# SP2_BUCKs_GPU_LOG_CPU-B.net
KiCad netlist of a schematic drawn in Altium Designer
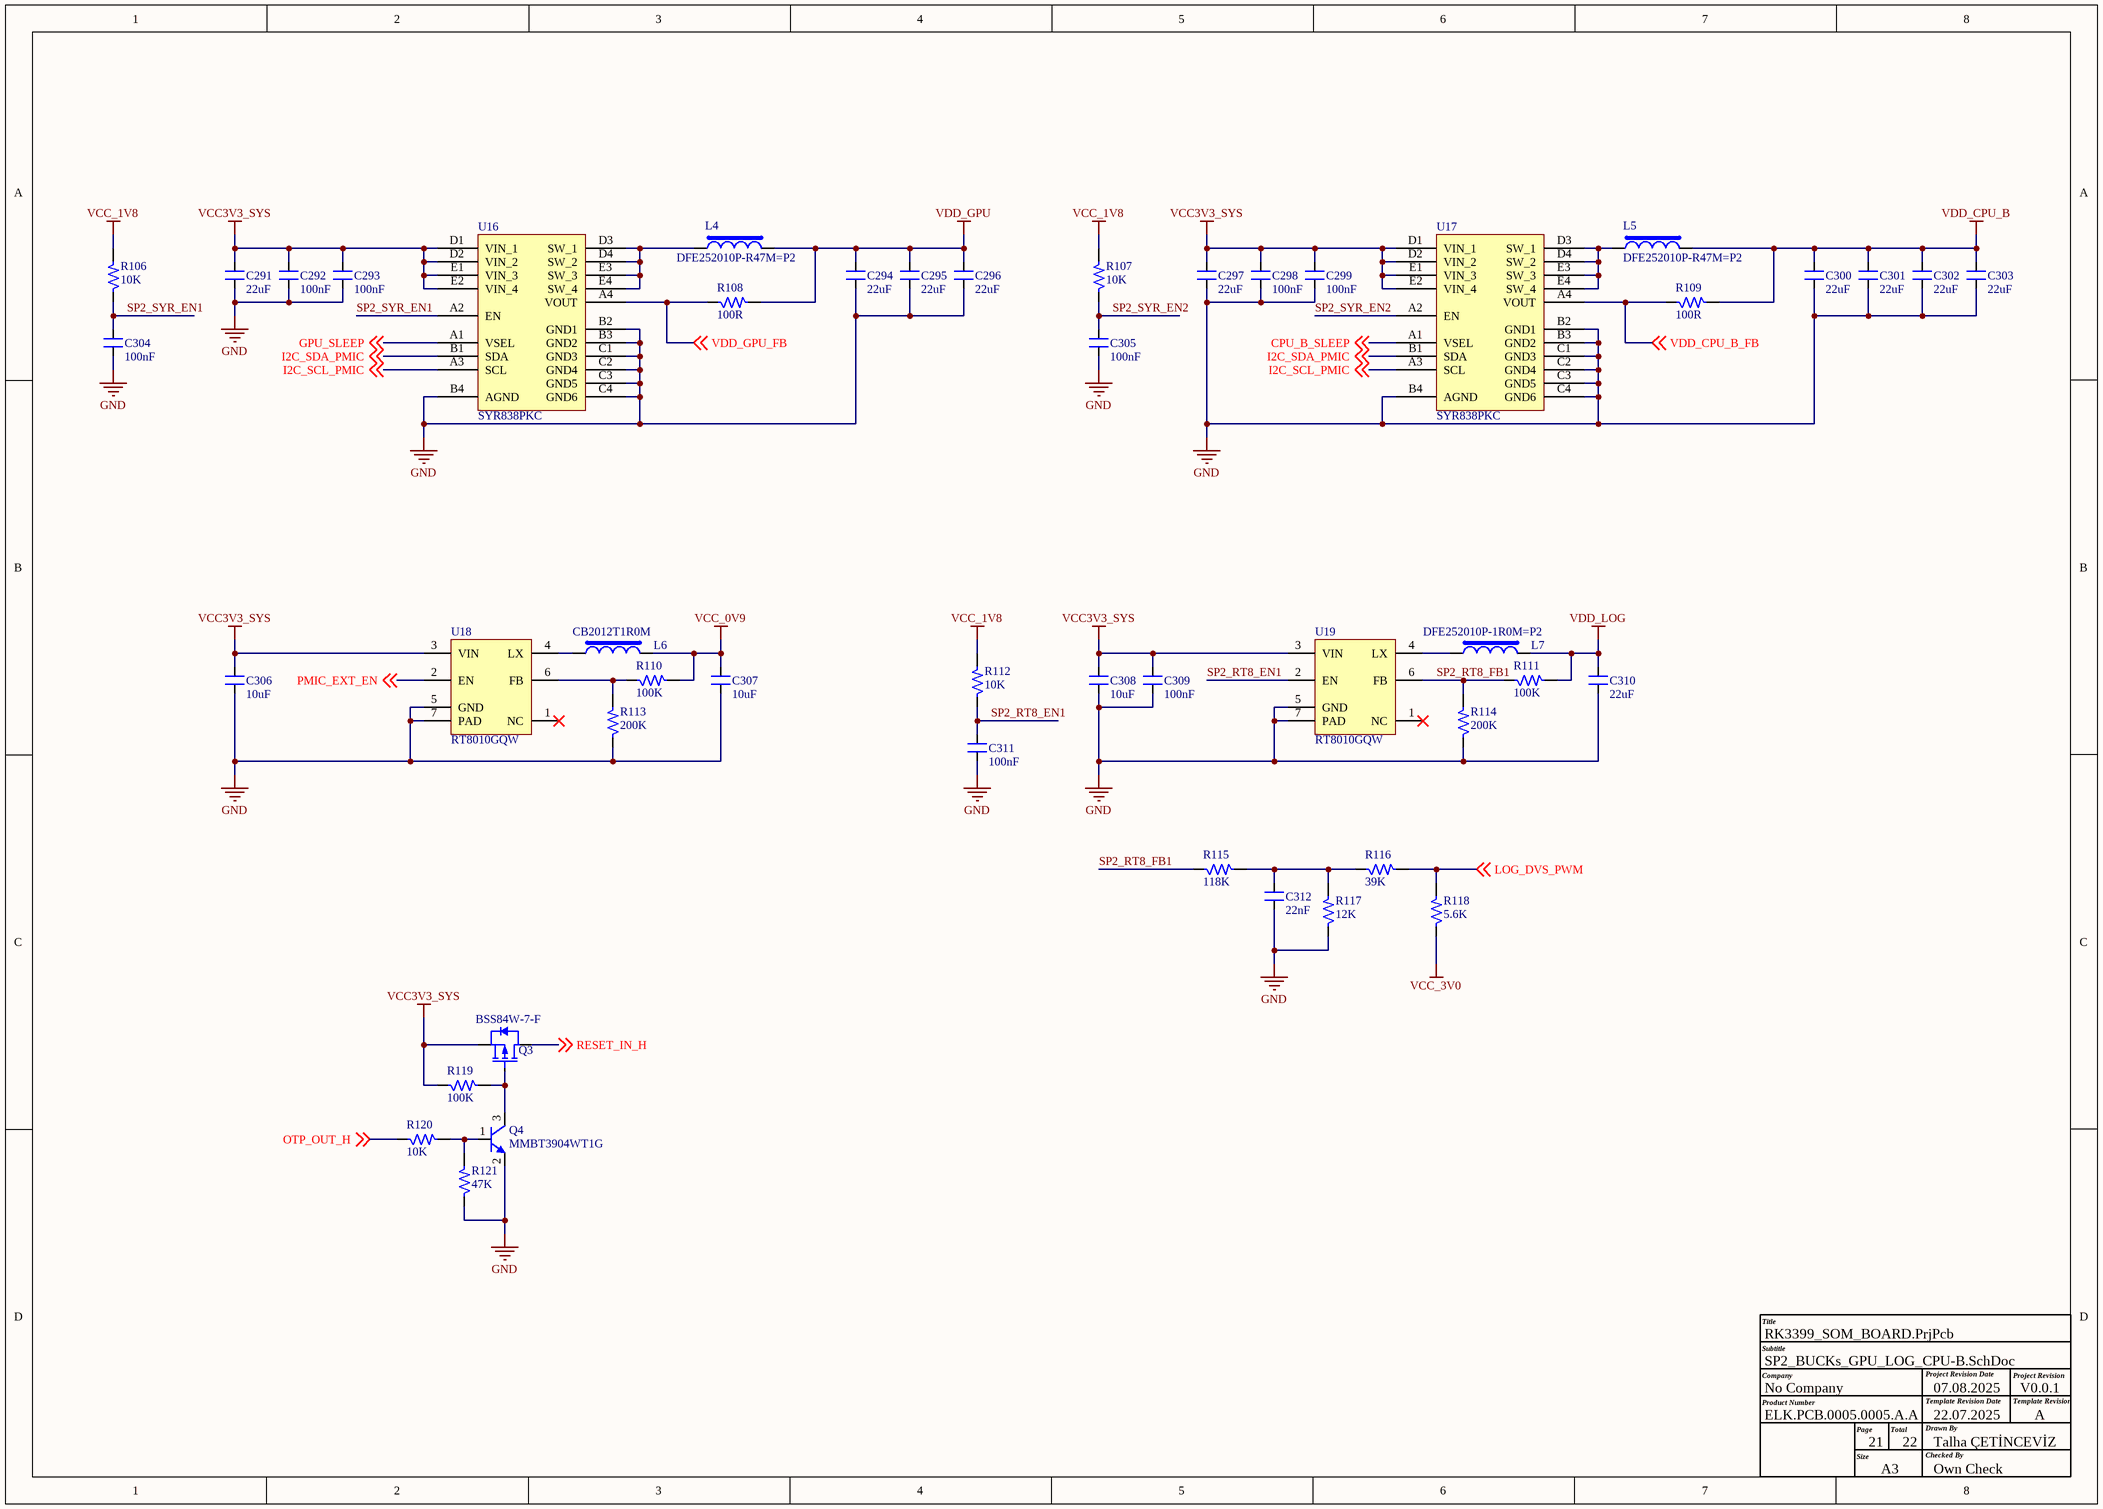
[diagram p0: SP2_BUCKs_GPU_LOG_CPU-B.SchDoc]

(export (version "E")
  (design (tool "Eeschema 10.0.6"))
  (components
    (comp (ref "C291")
      (value "22uF")
      (footprint "CAP_0603")
      (description "22µF ±20% 10V Ceramic Capacitor X5R 0603 (1608 Metric)")
      (fields
        (field (name "MANUFACTURER") "Murata Electronics")
        (field (name "MANUFACTURER PART NUMBER") "GRM188R61A226ME15D")
      )
      (libsource (lib "EsteemPCB_SOM_Course_intlib") (part "CAP_22uF-10V-20%-0603"))
    )
    (comp (ref "C292")
      (value "100nF")
      (footprint "CAP_0402")
      (description "0.1µF ±10% 25V Ceramic Capacitor X7R 0402 (1005 Metric)")
      (fields
        (field (name "MANUFACTURER") "Walsin Technology Corporation")
        (field (name "MANUFACTURER PART NUMBER") "0402B104K250CT")
      )
      (libsource (lib "EsteemPCB_SOM_Course_intlib") (part "CAP_100nF-25V-10%-0402"))
    )
    (comp (ref "C293")
      (value "100nF")
      (footprint "CAP_0402")
      (description "0.1µF ±10% 25V Ceramic Capacitor X7R 0402 (1005 Metric)")
      (fields
        (field (name "MANUFACTURER") "Walsin Technology Corporation")
        (field (name "MANUFACTURER PART NUMBER") "0402B104K250CT")
      )
      (libsource (lib "EsteemPCB_SOM_Course_intlib") (part "CAP_100nF-25V-10%-0402"))
    )
    (comp (ref "C294")
      (value "22uF")
      (footprint "CAP_0603")
      (description "22µF ±20% 10V Ceramic Capacitor X5R 0603 (1608 Metric)")
      (fields
        (field (name "MANUFACTURER") "Murata Electronics")
        (field (name "MANUFACTURER PART NUMBER") "GRM188R61A226ME15D")
      )
      (libsource (lib "EsteemPCB_SOM_Course_intlib") (part "CAP_22uF-10V-20%-0603"))
    )
    (comp (ref "C295")
      (value "22uF")
      (footprint "CAP_0603")
      (description "22µF ±20% 10V Ceramic Capacitor X5R 0603 (1608 Metric)")
      (fields
        (field (name "MANUFACTURER") "Murata Electronics")
        (field (name "MANUFACTURER PART NUMBER") "GRM188R61A226ME15D")
      )
      (libsource (lib "EsteemPCB_SOM_Course_intlib") (part "CAP_22uF-10V-20%-0603"))
    )
    (comp (ref "C296")
      (value "22uF")
      (footprint "CAP_0603")
      (description "22µF ±20% 10V Ceramic Capacitor X5R 0603 (1608 Metric)")
      (fields
        (field (name "MANUFACTURER") "Murata Electronics")
        (field (name "MANUFACTURER PART NUMBER") "GRM188R61A226ME15D")
      )
      (libsource (lib "EsteemPCB_SOM_Course_intlib") (part "CAP_22uF-10V-20%-0603"))
    )
    (comp (ref "C297")
      (value "22uF")
      (footprint "CAP_0603")
      (description "22µF ±20% 10V Ceramic Capacitor X5R 0603 (1608 Metric)")
      (fields
        (field (name "MANUFACTURER") "Murata Electronics")
        (field (name "MANUFACTURER PART NUMBER") "GRM188R61A226ME15D")
      )
      (libsource (lib "EsteemPCB_SOM_Course_intlib") (part "CAP_22uF-10V-20%-0603"))
    )
    (comp (ref "C298")
      (value "100nF")
      (footprint "CAP_0402")
      (description "0.1µF ±10% 25V Ceramic Capacitor X7R 0402 (1005 Metric)")
      (fields
        (field (name "MANUFACTURER") "Walsin Technology Corporation")
        (field (name "MANUFACTURER PART NUMBER") "0402B104K250CT")
      )
      (libsource (lib "EsteemPCB_SOM_Course_intlib") (part "CAP_100nF-25V-10%-0402"))
    )
    (comp (ref "C299")
      (value "100nF")
      (footprint "CAP_0402")
      (description "0.1µF ±10% 25V Ceramic Capacitor X7R 0402 (1005 Metric)")
      (fields
        (field (name "MANUFACTURER") "Walsin Technology Corporation")
        (field (name "MANUFACTURER PART NUMBER") "0402B104K250CT")
      )
      (libsource (lib "EsteemPCB_SOM_Course_intlib") (part "CAP_100nF-25V-10%-0402"))
    )
    (comp (ref "C300")
      (value "22uF")
      (footprint "CAP_0603")
      (description "22µF ±20% 10V Ceramic Capacitor X5R 0603 (1608 Metric)")
      (fields
        (field (name "MANUFACTURER") "Murata Electronics")
        (field (name "MANUFACTURER PART NUMBER") "GRM188R61A226ME15D")
      )
      (libsource (lib "EsteemPCB_SOM_Course_intlib") (part "CAP_22uF-10V-20%-0603"))
    )
    (comp (ref "C301")
      (value "22uF")
      (footprint "CAP_0603")
      (description "22µF ±20% 10V Ceramic Capacitor X5R 0603 (1608 Metric)")
      (fields
        (field (name "MANUFACTURER") "Murata Electronics")
        (field (name "MANUFACTURER PART NUMBER") "GRM188R61A226ME15D")
      )
      (libsource (lib "EsteemPCB_SOM_Course_intlib") (part "CAP_22uF-10V-20%-0603"))
    )
    (comp (ref "C302")
      (value "22uF")
      (footprint "CAP_0603")
      (description "22µF ±20% 10V Ceramic Capacitor X5R 0603 (1608 Metric)")
      (fields
        (field (name "MANUFACTURER") "Murata Electronics")
        (field (name "MANUFACTURER PART NUMBER") "GRM188R61A226ME15D")
      )
      (libsource (lib "EsteemPCB_SOM_Course_intlib") (part "CAP_22uF-10V-20%-0603"))
    )
    (comp (ref "C303")
      (value "22uF")
      (footprint "CAP_0603")
      (description "22µF ±20% 10V Ceramic Capacitor X5R 0603 (1608 Metric)")
      (fields
        (field (name "MANUFACTURER") "Murata Electronics")
        (field (name "MANUFACTURER PART NUMBER") "GRM188R61A226ME15D")
      )
      (libsource (lib "EsteemPCB_SOM_Course_intlib") (part "CAP_22uF-10V-20%-0603"))
    )
    (comp (ref "C304")
      (value "100nF")
      (footprint "CAP_0402")
      (description "0.1µF ±10% 25V Ceramic Capacitor X7R 0402 (1005 Metric)")
      (fields
        (field (name "MANUFACTURER") "Walsin Technology Corporation")
        (field (name "MANUFACTURER PART NUMBER") "0402B104K250CT")
      )
      (libsource (lib "EsteemPCB_SOM_Course_intlib") (part "CAP_100nF-25V-10%-0402"))
    )
    (comp (ref "C305")
      (value "100nF")
      (footprint "CAP_0402")
      (description "0.1µF ±10% 25V Ceramic Capacitor X7R 0402 (1005 Metric)")
      (fields
        (field (name "MANUFACTURER") "Walsin Technology Corporation")
        (field (name "MANUFACTURER PART NUMBER") "0402B104K250CT")
      )
      (libsource (lib "EsteemPCB_SOM_Course_intlib") (part "CAP_100nF-25V-10%-0402"))
    )
    (comp (ref "C306")
      (value "10uF")
      (footprint "CAP_0402")
      (description "10µF ±20% 10V Ceramic Capacitor X5R 0402 (1005 Metric)")
      (fields
        (field (name "MANUFACTURER PART NUMBER") "CL05A106MP5NUNC")
        (field (name "MANUFACTURER") "Samsung Electro-Mechanics")
      )
      (libsource (lib "EsteemPCB_SOM_Course_intlib") (part "CAP_10uF-10V-20%-0402"))
    )
    (comp (ref "C307")
      (value "10uF")
      (footprint "CAP_0402")
      (description "10µF ±20% 10V Ceramic Capacitor X5R 0402 (1005 Metric)")
      (fields
        (field (name "MANUFACTURER PART NUMBER") "CL05A106MP5NUNC")
        (field (name "MANUFACTURER") "Samsung Electro-Mechanics")
      )
      (libsource (lib "EsteemPCB_SOM_Course_intlib") (part "CAP_10uF-10V-20%-0402"))
    )
    (comp (ref "C308")
      (value "10uF")
      (footprint "CAP_0402")
      (description "10µF ±20% 10V Ceramic Capacitor X5R 0402 (1005 Metric)")
      (fields
        (field (name "MANUFACTURER PART NUMBER") "CL05A106MP5NUNC")
        (field (name "MANUFACTURER") "Samsung Electro-Mechanics")
      )
      (libsource (lib "EsteemPCB_SOM_Course_intlib") (part "CAP_10uF-10V-20%-0402"))
    )
    (comp (ref "C309")
      (value "100nF")
      (footprint "CAP_0402")
      (description "0.1µF ±10% 25V Ceramic Capacitor X7R 0402 (1005 Metric)")
      (fields
        (field (name "MANUFACTURER") "Walsin Technology Corporation")
        (field (name "MANUFACTURER PART NUMBER") "0402B104K250CT")
      )
      (libsource (lib "EsteemPCB_SOM_Course_intlib") (part "CAP_100nF-25V-10%-0402"))
    )
    (comp (ref "C310")
      (value "22uF")
      (footprint "CAP_0603")
      (description "22µF ±20% 10V Ceramic Capacitor X5R 0603 (1608 Metric)")
      (fields
        (field (name "MANUFACTURER") "Murata Electronics")
        (field (name "MANUFACTURER PART NUMBER") "GRM188R61A226ME15D")
      )
      (libsource (lib "EsteemPCB_SOM_Course_intlib") (part "CAP_22uF-10V-20%-0603"))
    )
    (comp (ref "C311")
      (value "100nF")
      (footprint "CAP_0402")
      (description "0.1µF ±10% 25V Ceramic Capacitor X7R 0402 (1005 Metric)")
      (fields
        (field (name "MANUFACTURER") "Walsin Technology Corporation")
        (field (name "MANUFACTURER PART NUMBER") "0402B104K250CT")
      )
      (libsource (lib "EsteemPCB_SOM_Course_intlib") (part "CAP_100nF-25V-10%-0402"))
    )
    (comp (ref "C312")
      (value "22nF")
      (footprint "CAP_0402")
      (description "0.022µF ±10% 10V Ceramic Capacitor X7R 0402 (1005 Metric)")
      (fields
        (field (name "MANUFACTURER") "Samsung Electro-Mechanics")
        (field (name "MANUFACTURER PART NUMBER") "CL05B223KP5NNNC")
      )
      (libsource (lib "EsteemPCB_SOM_Course_intlib") (part "CAP_22nF-10V-10%-0402"))
    )
    (comp (ref "L4")
      (value "DFE252010P-R47M=P2")
      (footprint "IND_1008")
      (description "470nH Shielded Wirewound Inductor 5A 35mOhm Max 1008 (2520 Metric)")
      (fields (field (name "MANUFACTURER") "Murata Electronics"))
      (libsource (lib "EsteemPCB_SOM_Course_intlib") (part "IND_470nH-5A-20%-1008"))
    )
    (comp (ref "L5")
      (value "DFE252010P-R47M=P2")
      (footprint "IND_1008")
      (description "470nH Shielded Wirewound Inductor 5A 35mOhm Max 1008 (2520 Metric)")
      (fields (field (name "MANUFACTURER") "Murata Electronics"))
      (libsource (lib "EsteemPCB_SOM_Course_intlib") (part "IND_470nH-5A-20%-1008"))
    )
    (comp (ref "L6")
      (value "CB2012T1R0M")
      (footprint "IND_0805")
      (description "1uH ±20% 500mA 150mΩ 0805 Inductors (SMD) RoHS")
      (fields (field (name "MANUFACTURER") "Taiyo Yuden"))
      (libsource (lib "EsteemPCB_SOM_Course_intlib") (part "IND_1uF-0.5A-20%-0805"))
    )
    (comp (ref "L7")
      (value "DFE252010P-1R0M=P2")
      (footprint "IND_1008")
      (description "1µH Shielded Wirewound Inductor 3.8A 54mOhm Max 1008 (2520 Metric)")
      (fields (field (name "MANUFACTURER") "Murata Electronics"))
      (libsource (lib "EsteemPCB_SOM_Course_intlib") (part "IND_1uH-3.8A-20%-1008"))
    )
    (comp (ref "Q3")
      (value "BSS84W-7-F")
      (footprint "SOT-323-3")
      (description "P-Channel 50V 130mA (Ta) 200mW (Ta) Surface Mount SOT-323")
      (fields (field (name "MANUFACTURER") "Diodes Incorporated"))
      (libsource (lib "EsteemPCB_SOM_Course_intlib") (part "MOSFET-P_50V-130mA-SOT-323"))
    )
    (comp (ref "Q4")
      (value "MMBT3904WT1G")
      (footprint "SOT-323-3")
      (description "Bipolar Transistors - BJT 200mA 60V NPN")
      (fields (field (name "MANUFACTURER") "ON Semiconductor"))
      (libsource (lib "EsteemPCB_SOM_Course_intlib") (part "TRNS-NPN_60V-0.2A-SOT323"))
    )
    (comp (ref "R106")
      (value "10K")
      (footprint "RES_0402")
      (description "10 kOhms ±1% 0.1W, 1/10W Chip Resistor 0402 (1005 Metric) Anti-Sulfur Thin Film")
      (fields
        (field (name "MANUFACTURER") "Vishay Beyschlag/Draloric/BC Components")
        (field (name "MANUFACTURER PART NUMBER") "MCS04020C1002FE000")
      )
      (libsource (lib "EsteemPCB_SOM_Course_intlib") (part "RES_10K-0.1W-1%-0402"))
    )
    (comp (ref "R107")
      (value "10K")
      (footprint "RES_0402")
      (description "10 kOhms ±1% 0.1W, 1/10W Chip Resistor 0402 (1005 Metric) Anti-Sulfur Thin Film")
      (fields
        (field (name "MANUFACTURER") "Vishay Beyschlag/Draloric/BC Components")
        (field (name "MANUFACTURER PART NUMBER") "MCS04020C1002FE000")
      )
      (libsource (lib "EsteemPCB_SOM_Course_intlib") (part "RES_10K-0.1W-1%-0402"))
    )
    (comp (ref "R108")
      (value "100R")
      (footprint "RES_0402")
      (fields
        (field (name "MANUFACTURER") "KOA Speer Electronics, Inc.")
        (field (name "MANUFACTURER PART NUMBER") "RK73H1ETTP1000F")
      )
      (libsource (lib "EsteemPCB_SOM_Course_intlib") (part "RES_100R-0.1W-1%-0402"))
    )
    (comp (ref "R109")
      (value "100R")
      (footprint "RES_0402")
      (fields
        (field (name "MANUFACTURER") "KOA Speer Electronics, Inc.")
        (field (name "MANUFACTURER PART NUMBER") "RK73H1ETTP1000F")
      )
      (libsource (lib "EsteemPCB_SOM_Course_intlib") (part "RES_100R-0.1W-1%-0402"))
    )
    (comp (ref "R110")
      (value "100K")
      (footprint "RES_0402")
      (description "100 kOhms ±1% 0.1W, 1/10W Chip Resistor 0402 (1005 Metric) Anti-Sulfur Thin Film")
      (fields
        (field (name "MANUFACTURER") "Vishay Beyschlag/Draloric/BC Components")
        (field (name "MANUFACTURER PART NUMBER") "MCS04020C1003FE000")
      )
      (libsource (lib "EsteemPCB_SOM_Course_intlib") (part "RES_100K-0.1W-1%-0402"))
    )
    (comp (ref "R111")
      (value "100K")
      (footprint "RES_0402")
      (description "100 kOhms ±1% 0.1W, 1/10W Chip Resistor 0402 (1005 Metric) Anti-Sulfur Thin Film")
      (fields
        (field (name "MANUFACTURER") "Vishay Beyschlag/Draloric/BC Components")
        (field (name "MANUFACTURER PART NUMBER") "MCS04020C1003FE000")
      )
      (libsource (lib "EsteemPCB_SOM_Course_intlib") (part "RES_100K-0.1W-1%-0402"))
    )
    (comp (ref "R112")
      (value "10K")
      (footprint "RES_0402")
      (description "10 kOhms ±1% 0.1W, 1/10W Chip Resistor 0402 (1005 Metric) Anti-Sulfur Thin Film")
      (fields
        (field (name "MANUFACTURER") "Vishay Beyschlag/Draloric/BC Components")
        (field (name "MANUFACTURER PART NUMBER") "MCS04020C1002FE000")
      )
      (libsource (lib "EsteemPCB_SOM_Course_intlib") (part "RES_10K-0.1W-1%-0402"))
    )
    (comp (ref "R113")
      (value "200K")
      (footprint "RES_0402")
      (description "200 kOhms ±1% 0.1W, 1/10W Chip Resistor 0402 (1005 Metric) Automotive AEC-Q200 Thick Film")
      (fields
        (field (name "MANUFACTURER") "Panasonic Electronic Components")
        (field (name "MANUFACTURER PART NUMBER") "ERJ-2RKF2003X")
      )
      (libsource (lib "EsteemPCB_SOM_Course_intlib") (part "RES_200K-0.1W-1%-0402"))
    )
    (comp (ref "R114")
      (value "200K")
      (footprint "RES_0402")
      (description "200 kOhms ±1% 0.1W, 1/10W Chip Resistor 0402 (1005 Metric) Automotive AEC-Q200 Thick Film")
      (fields
        (field (name "MANUFACTURER") "Panasonic Electronic Components")
        (field (name "MANUFACTURER PART NUMBER") "ERJ-2RKF2003X")
      )
      (libsource (lib "EsteemPCB_SOM_Course_intlib") (part "RES_200K-0.1W-1%-0402"))
    )
    (comp (ref "R115")
      (value "118K")
      (footprint "RES_0402")
      (fields
        (field (name "MANUFACTURER") "KOA Speer Electronics, Inc.")
        (field (name "MANUAFCTURER PART NUMBER") "RK73H1ETTP1183F")
      )
      (libsource (lib "EsteemPCB_SOM_Course_intlib") (part "RES_118K-0.1W-1%-0402"))
    )
    (comp (ref "R116")
      (value "39K")
      (footprint "RES_0402")
      (fields
        (field (name "MANUFACTURER") "KOA Speer Electronics, Inc.")
        (field (name "MANUFACTURER PART NUMBER") "RK73H1ETTP3902F")
      )
      (libsource (lib "EsteemPCB_SOM_Course_intlib") (part "RES_39K-0.1W-1%-0402"))
    )
    (comp (ref "R117")
      (value "12K")
      (footprint "RES_0402")
      (description "12 kOhms ±1% 0.1W, 1/10W Chip Resistor 0402 (1005 Metric) Anti-Sulfur Thin Film")
      (fields
        (field (name "MANUFACTURER") "Vishay Beyschlag/Draloric/BC Components")
        (field (name "MANUFACTURER PART NUMBER") "MCS04020C1202FE000")
      )
      (libsource (lib "EsteemPCB_SOM_Course_intlib") (part "RES_12K-0.1W-1%-0402"))
    )
    (comp (ref "R118")
      (value "5.6K")
      (footprint "RES_0402")
      (fields
        (field (name "MANUFACTURER") "KOA Speer Electronics, Inc.")
        (field (name "MANUFACTURER PART NUMBER") "RK73H1ETTP5601F")
      )
      (libsource (lib "EsteemPCB_SOM_Course_intlib") (part "RES_5.6K-0.1W-1%-0402"))
    )
    (comp (ref "R119")
      (value "100K")
      (footprint "RES_0402")
      (description "100 kOhms ±1% 0.1W, 1/10W Chip Resistor 0402 (1005 Metric) Anti-Sulfur Thin Film")
      (fields
        (field (name "MANUFACTURER") "Vishay Beyschlag/Draloric/BC Components")
        (field (name "MANUFACTURER PART NUMBER") "MCS04020C1003FE000")
      )
      (libsource (lib "EsteemPCB_SOM_Course_intlib") (part "RES_100K-0.1W-1%-0402"))
    )
    (comp (ref "R120")
      (value "10K")
      (footprint "RES_0402")
      (description "10 kOhms ±1% 0.1W, 1/10W Chip Resistor 0402 (1005 Metric) Anti-Sulfur Thin Film")
      (fields
        (field (name "MANUFACTURER") "Vishay Beyschlag/Draloric/BC Components")
        (field (name "MANUFACTURER PART NUMBER") "MCS04020C1002FE000")
      )
      (libsource (lib "EsteemPCB_SOM_Course_intlib") (part "RES_10K-0.1W-1%-0402"))
    )
    (comp (ref "R121")
      (value "47K")
      (footprint "RES_0402")
      (description "47 kOhms ±1% 0.1W, 1/10W Chip Resistor 0402 (1005 Metric) Automotive AEC-Q200 Thick Film")
      (fields
        (field (name "MANUFACTURER") "Panasonic Electronic Components")
        (field (name "MANUFACTURER PART NUMBER") "ERJ-2RKF4702X")
      )
      (libsource (lib "EsteemPCB_SOM_Course_intlib") (part "RES_47K-0.1W-1%-0402"))
    )
    (comp (ref "U16")
      (value "SYR838PKC")
      (footprint "CSP20_15.7_100x84_SMD")
      (description "Step-Down Positive Programmable 1 6A 2.4MHz CSP1.56*1.96-20 DC-DC Converters RoHS")
      (fields (field (name "MANUFACTURER") "Silergy Corp"))
      (libsource (lib "EsteemPCB_SOM_Course_intlib") (part "IC_SYR838PKC"))
    )
    (comp (ref "U17")
      (value "SYR838PKC")
      (footprint "CSP20_15.7_100x84_SMD")
      (description "Step-Down Positive Programmable 1 6A 2.4MHz CSP1.56*1.96-20 DC-DC Converters RoHS")
      (fields (field (name "MANUFACTURER") "Silergy Corp"))
      (libsource (lib "EsteemPCB_SOM_Course_intlib") (part "IC_SYR838PKC"))
    )
    (comp (ref "U18")
      (value "RT8010GQW")
      (footprint "WDFN-6_26_133X100_SMD")
      (description "Buck Switching Regulator IC Positive Adjustable 0.6V 1 Output 1A 6-WDFN Exposed Pad")
      (fields (field (name "MANUFACTURER") "Richtek USA Inc."))
      (libsource (lib "EsteemPCB_SOM_Course_intlib") (part "REG-ADJ_5.5V-5.5V-1A-6-WDFN"))
    )
    (comp (ref "U19")
      (value "RT8010GQW")
      (footprint "WDFN-6_26_133X100_SMD")
      (description "Buck Switching Regulator IC Positive Adjustable 0.6V 1 Output 1A 6-WDFN Exposed Pad")
      (fields (field (name "MANUFACTURER") "Richtek USA Inc."))
      (libsource (lib "EsteemPCB_SOM_Course_intlib") (part "REG-ADJ_5.5V-5.5V-1A-6-WDFN"))
    )
  )
  (nets
    (net (code "1") (name "/SP2_RT8_EN1") (class "Default")
      (node (ref "C311") (pin "2") (pinfunction "2_2") (pintype "passive"))
      (node (ref "R112") (pin "1") (pinfunction "1_1") (pintype "passive"))
      (node (ref "U19") (pin "2") (pinfunction "EN_2") (pintype "passive"))
    )
    (net (code "2") (name "/SP2_RT8_FB1") (class "Default")
      (node (ref "R111") (pin "1") (pinfunction "1_1") (pintype "passive"))
      (node (ref "R114") (pin "2") (pinfunction "2_2") (pintype "passive"))
      (node (ref "R115") (pin "1") (pinfunction "1_1") (pintype "passive"))
      (node (ref "U19") (pin "6") (pinfunction "FB_6") (pintype "passive"))
    )
    (net (code "3") (name "/SP2_SYR_EN1") (class "Default")
      (node (ref "C304") (pin "2") (pinfunction "2_2") (pintype "passive"))
      (node (ref "R106") (pin "1") (pinfunction "1_1") (pintype "passive"))
      (node (ref "U16") (pin "A2") (pinfunction "EN_A2") (pintype "passive"))
    )
    (net (code "4") (name "/SP2_SYR_EN2") (class "Default")
      (node (ref "C305") (pin "2") (pinfunction "2_2") (pintype "passive"))
      (node (ref "R107") (pin "1") (pinfunction "1_1") (pintype "passive"))
      (node (ref "U17") (pin "A2") (pinfunction "EN_A2") (pintype "passive"))
    )
    (net (code "5") (name "CPU_B_SLEEP") (class "Default")
      (node (ref "U17") (pin "A1") (pinfunction "VSEL_A1") (pintype "passive"))
    )
    (net (code "6") (name "GND") (class "Default")
      (node (ref "C291") (pin "1") (pinfunction "1_1") (pintype "passive"))
      (node (ref "C292") (pin "1") (pinfunction "1_1") (pintype "passive"))
      (node (ref "C293") (pin "1") (pinfunction "1_1") (pintype "passive"))
      (node (ref "C294") (pin "1") (pinfunction "1_1") (pintype "passive"))
      (node (ref "C295") (pin "1") (pinfunction "1_1") (pintype "passive"))
      (node (ref "C296") (pin "1") (pinfunction "1_1") (pintype "passive"))
      (node (ref "C297") (pin "1") (pinfunction "1_1") (pintype "passive"))
      (node (ref "C298") (pin "1") (pinfunction "1_1") (pintype "passive"))
      (node (ref "C299") (pin "1") (pinfunction "1_1") (pintype "passive"))
      (node (ref "C300") (pin "1") (pinfunction "1_1") (pintype "passive"))
      (node (ref "C301") (pin "1") (pinfunction "1_1") (pintype "passive"))
      (node (ref "C302") (pin "1") (pinfunction "1_1") (pintype "passive"))
      (node (ref "C303") (pin "1") (pinfunction "1_1") (pintype "passive"))
      (node (ref "C304") (pin "1") (pinfunction "1_1") (pintype "passive"))
      (node (ref "C305") (pin "1") (pinfunction "1_1") (pintype "passive"))
      (node (ref "C306") (pin "1") (pinfunction "1_1") (pintype "passive"))
      (node (ref "C307") (pin "1") (pinfunction "1_1") (pintype "passive"))
      (node (ref "C308") (pin "1") (pinfunction "1_1") (pintype "passive"))
      (node (ref "C309") (pin "1") (pinfunction "1_1") (pintype "passive"))
      (node (ref "C310") (pin "1") (pinfunction "1_1") (pintype "passive"))
      (node (ref "C311") (pin "1") (pinfunction "1_1") (pintype "passive"))
      (node (ref "C312") (pin "1") (pinfunction "1_1") (pintype "passive"))
      (node (ref "Q4") (pin "2") (pinfunction "E_2") (pintype "passive"))
      (node (ref "R113") (pin "1") (pinfunction "1_1") (pintype "passive"))
      (node (ref "R114") (pin "1") (pinfunction "1_1") (pintype "passive"))
      (node (ref "R117") (pin "1") (pinfunction "1_1") (pintype "passive"))
      (node (ref "R121") (pin "1") (pinfunction "1_1") (pintype "passive"))
      (node (ref "U16") (pin "B2") (pinfunction "GND1_B2") (pintype "passive"))
      (node (ref "U16") (pin "B3") (pinfunction "GND2_B3") (pintype "passive"))
      (node (ref "U16") (pin "B4") (pinfunction "AGND_B4") (pintype "passive"))
      (node (ref "U16") (pin "C1") (pinfunction "GND3_C1") (pintype "passive"))
      (node (ref "U16") (pin "C2") (pinfunction "GND4_C2") (pintype "passive"))
      (node (ref "U16") (pin "C3") (pinfunction "GND5_C3") (pintype "passive"))
      (node (ref "U16") (pin "C4") (pinfunction "GND6_C4") (pintype "passive"))
      (node (ref "U17") (pin "B2") (pinfunction "GND1_B2") (pintype "passive"))
      (node (ref "U17") (pin "B3") (pinfunction "GND2_B3") (pintype "passive"))
      (node (ref "U17") (pin "B4") (pinfunction "AGND_B4") (pintype "passive"))
      (node (ref "U17") (pin "C1") (pinfunction "GND3_C1") (pintype "passive"))
      (node (ref "U17") (pin "C2") (pinfunction "GND4_C2") (pintype "passive"))
      (node (ref "U17") (pin "C3") (pinfunction "GND5_C3") (pintype "passive"))
      (node (ref "U17") (pin "C4") (pinfunction "GND6_C4") (pintype "passive"))
      (node (ref "U18") (pin "5") (pinfunction "GND_5") (pintype "passive"))
      (node (ref "U18") (pin "7") (pinfunction "PAD_7") (pintype "passive"))
      (node (ref "U19") (pin "5") (pinfunction "GND_5") (pintype "passive"))
      (node (ref "U19") (pin "7") (pinfunction "PAD_7") (pintype "passive"))
    )
    (net (code "7") (name "GPU_SLEEP") (class "Default")
      (node (ref "U16") (pin "A1") (pinfunction "VSEL_A1") (pintype "passive"))
    )
    (net (code "8") (name "I2C_SCL_PMIC") (class "Default")
      (node (ref "U16") (pin "A3") (pinfunction "SCL_A3") (pintype "passive"))
      (node (ref "U17") (pin "A3") (pinfunction "SCL_A3") (pintype "passive"))
    )
    (net (code "9") (name "I2C_SDA_PMIC") (class "Default")
      (node (ref "U16") (pin "B1") (pinfunction "SDA_B1") (pintype "passive"))
      (node (ref "U17") (pin "B1") (pinfunction "SDA_B1") (pintype "passive"))
    )
    (net (code "10") (name "LOG_DVS_PWM") (class "Default")
      (node (ref "R116") (pin "2") (pinfunction "2_2") (pintype "passive"))
      (node (ref "R118") (pin "2") (pinfunction "2_2") (pintype "passive"))
    )
    (net (code "11") (name "Net-(C312-Pad2)") (class "Default")
      (node (ref "C312") (pin "2") (pinfunction "2_2") (pintype "passive"))
      (node (ref "R115") (pin "2") (pinfunction "2_2") (pintype "passive"))
      (node (ref "R116") (pin "1") (pinfunction "1_1") (pintype "passive"))
      (node (ref "R117") (pin "2") (pinfunction "2_2") (pintype "passive"))
    )
    (net (code "12") (name "Net-(Q3-G)") (class "Default")
      (node (ref "Q3") (pin "1") (pinfunction "G_1") (pintype "passive"))
      (node (ref "Q4") (pin "3") (pinfunction "C_3") (pintype "passive"))
      (node (ref "R119") (pin "2") (pinfunction "2_2") (pintype "passive"))
    )
    (net (code "13") (name "Net-(Q4-B)") (class "Default")
      (node (ref "Q4") (pin "1") (pinfunction "B_1") (pintype "passive"))
      (node (ref "R120") (pin "2") (pinfunction "2_2") (pintype "passive"))
      (node (ref "R121") (pin "2") (pinfunction "2_2") (pintype "passive"))
    )
    (net (code "14") (name "Net-(U16-SW_1)") (class "Default")
      (node (ref "L4") (pin "1") (pinfunction "1_1") (pintype "passive"))
      (node (ref "U16") (pin "D3") (pinfunction "SW_1_D3") (pintype "passive"))
      (node (ref "U16") (pin "D4") (pinfunction "SW_2_D4") (pintype "passive"))
      (node (ref "U16") (pin "E3") (pinfunction "SW_3_E3") (pintype "passive"))
      (node (ref "U16") (pin "E4") (pinfunction "SW_4_E4") (pintype "passive"))
    )
    (net (code "15") (name "Net-(U17-SW_1)") (class "Default")
      (node (ref "L5") (pin "1") (pinfunction "1_1") (pintype "passive"))
      (node (ref "U17") (pin "D3") (pinfunction "SW_1_D3") (pintype "passive"))
      (node (ref "U17") (pin "D4") (pinfunction "SW_2_D4") (pintype "passive"))
      (node (ref "U17") (pin "E3") (pinfunction "SW_3_E3") (pintype "passive"))
      (node (ref "U17") (pin "E4") (pinfunction "SW_4_E4") (pintype "passive"))
    )
    (net (code "16") (name "Net-(U18-FB)") (class "Default")
      (node (ref "R110") (pin "1") (pinfunction "1_1") (pintype "passive"))
      (node (ref "R113") (pin "2") (pinfunction "2_2") (pintype "passive"))
      (node (ref "U18") (pin "6") (pinfunction "FB_6") (pintype "passive"))
    )
    (net (code "17") (name "Net-(U18-LX)") (class "Default")
      (node (ref "L6") (pin "1") (pinfunction "1_1") (pintype "passive"))
      (node (ref "U18") (pin "4") (pinfunction "LX_4") (pintype "passive"))
    )
    (net (code "18") (name "Net-(U19-LX)") (class "Default")
      (node (ref "L7") (pin "1") (pinfunction "1_1") (pintype "passive"))
      (node (ref "U19") (pin "4") (pinfunction "LX_4") (pintype "passive"))
    )
    (net (code "19") (name "OTP_OUT_H") (class "Default")
      (node (ref "R120") (pin "1") (pinfunction "1_1") (pintype "passive"))
    )
    (net (code "20") (name "PMIC_EXT_EN") (class "Default")
      (node (ref "U18") (pin "2") (pinfunction "EN_2") (pintype "passive"))
    )
    (net (code "21") (name "RESET_IN_H") (class "Default")
      (node (ref "Q3") (pin "3") (pinfunction "D_3") (pintype "passive"))
    )
    (net (code "22") (name "VCC3V3_SYS") (class "Default")
      (node (ref "C291") (pin "2") (pinfunction "2_2") (pintype "passive"))
      (node (ref "C292") (pin "2") (pinfunction "2_2") (pintype "passive"))
      (node (ref "C293") (pin "2") (pinfunction "2_2") (pintype "passive"))
      (node (ref "C297") (pin "2") (pinfunction "2_2") (pintype "passive"))
      (node (ref "C298") (pin "2") (pinfunction "2_2") (pintype "passive"))
      (node (ref "C299") (pin "2") (pinfunction "2_2") (pintype "passive"))
      (node (ref "C306") (pin "2") (pinfunction "2_2") (pintype "passive"))
      (node (ref "C308") (pin "2") (pinfunction "2_2") (pintype "passive"))
      (node (ref "C309") (pin "2") (pinfunction "2_2") (pintype "passive"))
      (node (ref "Q3") (pin "2") (pinfunction "S_2") (pintype "passive"))
      (node (ref "R119") (pin "1") (pinfunction "1_1") (pintype "passive"))
      (node (ref "U16") (pin "D1") (pinfunction "VIN_1_D1") (pintype "passive"))
      (node (ref "U16") (pin "D2") (pinfunction "VIN_2_D2") (pintype "passive"))
      (node (ref "U16") (pin "E1") (pinfunction "VIN_3_E1") (pintype "passive"))
      (node (ref "U16") (pin "E2") (pinfunction "VIN_4_E2") (pintype "passive"))
      (node (ref "U17") (pin "D1") (pinfunction "VIN_1_D1") (pintype "passive"))
      (node (ref "U17") (pin "D2") (pinfunction "VIN_2_D2") (pintype "passive"))
      (node (ref "U17") (pin "E1") (pinfunction "VIN_3_E1") (pintype "passive"))
      (node (ref "U17") (pin "E2") (pinfunction "VIN_4_E2") (pintype "passive"))
      (node (ref "U18") (pin "3") (pinfunction "VIN_3") (pintype "passive"))
      (node (ref "U19") (pin "3") (pinfunction "VIN_3") (pintype "passive"))
    )
    (net (code "23") (name "VCC_0V9") (class "Default")
      (node (ref "C307") (pin "2") (pinfunction "2_2") (pintype "passive"))
      (node (ref "L6") (pin "2") (pinfunction "2_2") (pintype "passive"))
      (node (ref "R110") (pin "2") (pinfunction "2_2") (pintype "passive"))
    )
    (net (code "24") (name "VCC_1V8") (class "Default")
      (node (ref "R106") (pin "2") (pinfunction "2_2") (pintype "passive"))
      (node (ref "R107") (pin "2") (pinfunction "2_2") (pintype "passive"))
      (node (ref "R112") (pin "2") (pinfunction "2_2") (pintype "passive"))
    )
    (net (code "25") (name "VCC_3V0") (class "Default")
      (node (ref "R118") (pin "1") (pinfunction "1_1") (pintype "passive"))
    )
    (net (code "26") (name "VDD_CPU_B") (class "Default")
      (node (ref "C300") (pin "2") (pinfunction "2_2") (pintype "passive"))
      (node (ref "C301") (pin "2") (pinfunction "2_2") (pintype "passive"))
      (node (ref "C302") (pin "2") (pinfunction "2_2") (pintype "passive"))
      (node (ref "C303") (pin "2") (pinfunction "2_2") (pintype "passive"))
      (node (ref "L5") (pin "2") (pinfunction "2_2") (pintype "passive"))
      (node (ref "R109") (pin "2") (pinfunction "2_2") (pintype "passive"))
    )
    (net (code "27") (name "VDD_CPU_B_FB") (class "Default")
      (node (ref "R109") (pin "1") (pinfunction "1_1") (pintype "passive"))
      (node (ref "U17") (pin "A4") (pinfunction "VOUT_A4") (pintype "passive"))
    )
    (net (code "28") (name "VDD_GPU") (class "Default")
      (node (ref "C294") (pin "2") (pinfunction "2_2") (pintype "passive"))
      (node (ref "C295") (pin "2") (pinfunction "2_2") (pintype "passive"))
      (node (ref "C296") (pin "2") (pinfunction "2_2") (pintype "passive"))
      (node (ref "L4") (pin "2") (pinfunction "2_2") (pintype "passive"))
      (node (ref "R108") (pin "2") (pinfunction "2_2") (pintype "passive"))
    )
    (net (code "29") (name "VDD_GPU_FB") (class "Default")
      (node (ref "R108") (pin "1") (pinfunction "1_1") (pintype "passive"))
      (node (ref "U16") (pin "A4") (pinfunction "VOUT_A4") (pintype "passive"))
    )
    (net (code "30") (name "VDD_LOG") (class "Default")
      (node (ref "C310") (pin "2") (pinfunction "2_2") (pintype "passive"))
      (node (ref "L7") (pin "2") (pinfunction "2_2") (pintype "passive"))
      (node (ref "R111") (pin "2") (pinfunction "2_2") (pintype "passive"))
    )
    (net (code "31") (name "unconnected-(U18-NC-Pad1)") (class "Default")
      (node (ref "U18") (pin "1") (pinfunction "NC_1") (pintype "passive+no_connect"))
    )
    (net (code "32") (name "unconnected-(U19-NC-Pad1)") (class "Default")
      (node (ref "U19") (pin "1") (pinfunction "NC_1") (pintype "passive+no_connect"))
    )
  )
)
